# Power.net
KiCad netlist of a schematic drawn in Altium Designer
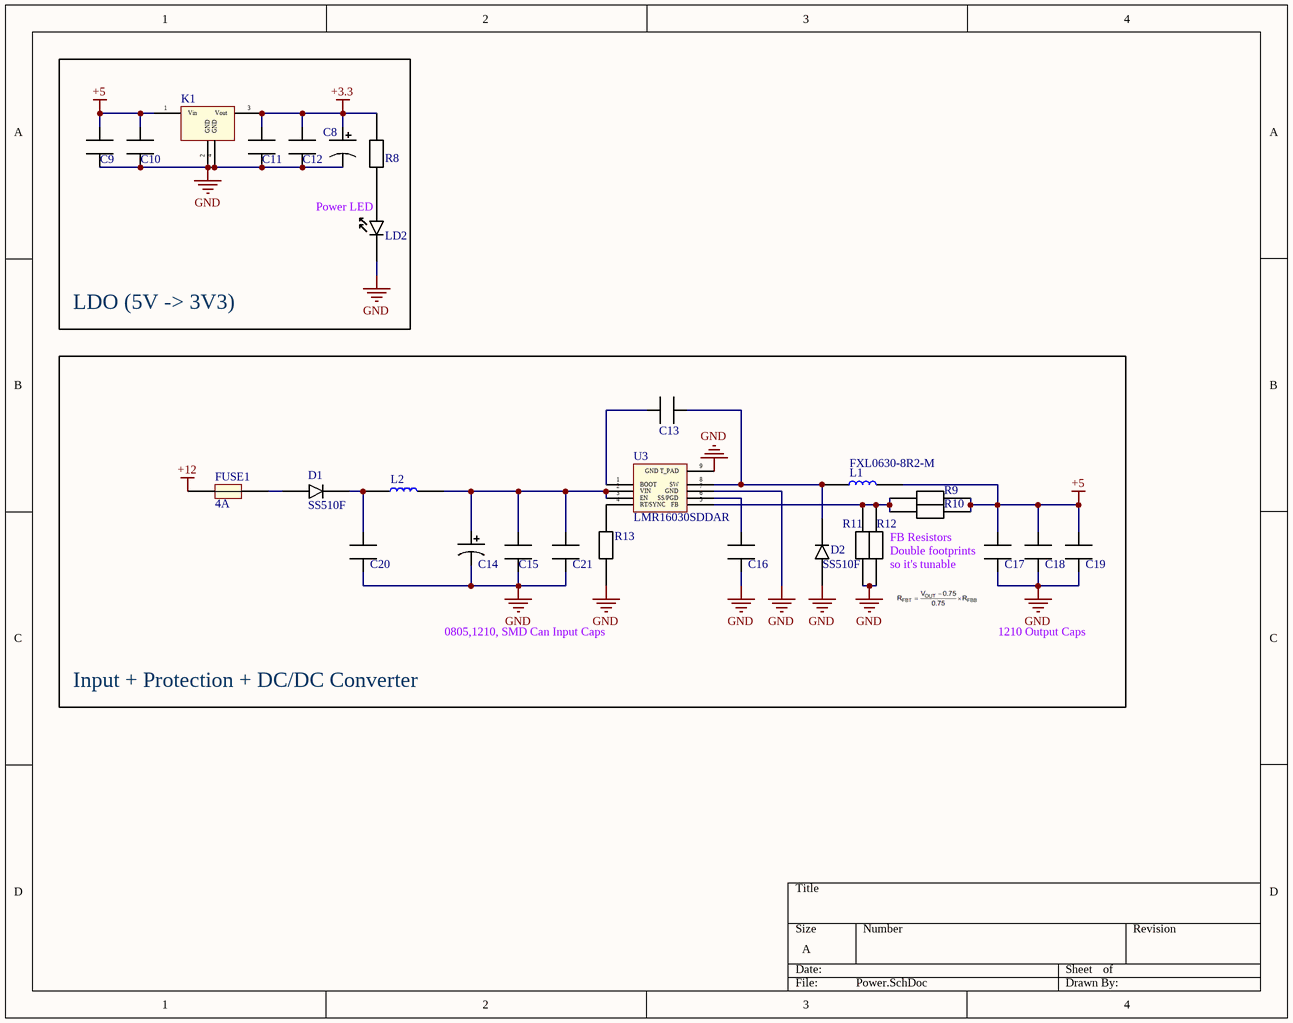
[diagram p0: Power.SchDoc]

(export (version "E")
  (design (tool "Eeschema 10.0.6"))
  (components
    (comp (ref "C8")
      (value "10uf")
      (footprint "CAP_CAN_D5MM")
      (description "SMD Can Capacitor; 5mm Diameter")
      (libsource (lib "Passives") (part "CAP_CAN_D5mm"))
    )
    (comp (ref "C9")
      (value "1uF")
      (footprint "CAP_1206")
      (description "CAP_1206")
      (libsource (lib "Passives") (part "CAP_1206"))
    )
    (comp (ref "C10")
      (value "100nF")
      (footprint "CAP_0805")
      (description "CAP_0805")
      (libsource (lib "Passives") (part "CAP_0805"))
    )
    (comp (ref "C11")
      (value "100nF")
      (footprint "CAP_0805")
      (description "CAP_0805")
      (libsource (lib "Passives") (part "CAP_0805"))
    )
    (comp (ref "C12")
      (value "1uF")
      (footprint "CAP_1206")
      (description "CAP_1206")
      (libsource (lib "Passives") (part "CAP_1206"))
    )
    (comp (ref "C13")
      (value "100nF 50V")
      (footprint "CAP_0805")
      (description "CAP_0805")
      (libsource (lib "Passives") (part "CAP_0805"))
    )
    (comp (ref "C14")
      (value "47uf 100v")
      (footprint "CAP_CAN_D10mm")
      (description "SMD Can Capacitor; 10mm Diameter")
      (libsource (lib "Passives") (part "CAP_CAN_D10mm"))
    )
    (comp (ref "C15")
      (value "10uF 100V")
      (footprint "CAP_1210")
      (description "CAP_1210")
      (libsource (lib "Passives") (part "CAP_1210"))
    )
    (comp (ref "C16")
      (value "100nF 50V")
      (footprint "CAP_0805")
      (description "CAP_0805")
      (libsource (lib "Passives") (part "CAP_0805"))
    )
    (comp (ref "C17")
      (value "CS3225X7R476K160NRL")
      (footprint "CAP_1210")
      (description "CAP_1210")
      (libsource (lib "Passives") (part "CAP_1210"))
    )
    (comp (ref "C18")
      (value "CS3225X7R476K160NRL")
      (footprint "CAP_1210")
      (description "CAP_1210")
      (libsource (lib "Passives") (part "CAP_1210"))
    )
    (comp (ref "C19")
      (value "CS3225X7R476K160NRL")
      (footprint "CAP_1210")
      (description "CAP_1210")
      (libsource (lib "Passives") (part "CAP_1210"))
    )
    (comp (ref "C20")
      (value "100nF 100V")
      (footprint "CAP_0805")
      (description "CAP_0805")
      (libsource (lib "Passives") (part "CAP_0805"))
    )
    (comp (ref "C21")
      (value "100nF 100V")
      (footprint "CAP_0805")
      (description "CAP_0805")
      (libsource (lib "Passives") (part "CAP_0805"))
    )
    (comp (ref "D1")
      (value "SS510F")
      (footprint "SMAF")
      (description "100V 850mV@5A 5A SMAF Schottky Diodes ROHS")
      (libsource (lib "Diodes") (part "SS510F"))
    )
    (comp (ref "D2")
      (value "SS510F")
      (footprint "SMAF")
      (description "100V 850mV@5A 5A SMAF Schottky Diodes ROHS")
      (libsource (lib "Diodes") (part "SS510F"))
    )
    (comp (ref "FUSE1")
      (value "4A")
      (footprint "FUSE_1206")
      (description "Fuse_1206")
      (libsource (lib "Passives") (part "Fuse_1206"))
    )
    (comp (ref "K1")
      (value "MIC39100-3.3WS")
      (footprint "SOT223-4")
      (description "LDO; \r\n2.25V -> 16V;\r\n1A Max; \r\nFixed Output - 1.8V, 2.5V, 3.3V, 5V")
      (libsource (lib "IC_Power") (part "MIC39100_SOT223"))
    )
    (comp (ref "L1")
      (value "FXL0630-8R2-M")
      (footprint "IND_FXL06")
      (description "Precision Wire Wound Inductor, 2-Leads, Body 4,50x4,00mm, IPC Medium Density")
      (libsource (lib "Passives") (part "IND_FXL06"))
    )
    (comp (ref "L2")
      (value "10uH 1.2A")
      (footprint "IND_1210")
      (description "Precision Wire Wound Inductor, 2-Leads, Body 4,50x4,00mm, IPC Medium Density")
      (libsource (lib "Passives") (part "IND_1210_Choke"))
    )
    (comp (ref "LD2")
      (value "LED_0805")
      (footprint "LED_0805")
      (libsource (lib "Passives") (part "LED_0805"))
    )
    (comp (ref "R8")
      (value "10k")
      (footprint "RES_0805")
      (description "RES_0805")
      (libsource (lib "Passives") (part "RES_0805"))
    )
    (comp (ref "R9")
      (value "10k")
      (footprint "RES_0805")
      (description "RES_0805")
      (libsource (lib "Passives") (part "RES_0805"))
    )
    (comp (ref "R10")
      (value "NC")
      (footprint "RES_0805")
      (description "RES_0805")
      (libsource (lib "Passives") (part "RES_0805"))
    )
    (comp (ref "R11")
      (value "2k")
      (footprint "RES_0805")
      (description "RES_0805")
      (libsource (lib "Passives") (part "RES_0805"))
    )
    (comp (ref "R12")
      (value "15k")
      (footprint "RES_0805")
      (description "RES_0805")
      (libsource (lib "Passives") (part "RES_0805"))
    )
    (comp (ref "R13")
      (value "10k")
      (footprint "RES_0805")
      (description "RES_0805")
      (libsource (lib "Passives") (part "RES_0805"))
    )
    (comp (ref "U3")
      (value "LMR16030SDDAR")
      (footprint "SOIC8_T")
      (libsource (lib "IC_Power") (part "TI LMR16030SDDAR"))
    )
  )
  (nets
    (net (code "1") (name "+3.3") (class "Default")
      (node (ref "C11") (pin "2") (pinfunction "2_2") (pintype "passive"))
      (node (ref "C12") (pin "2") (pinfunction "2_2") (pintype "passive"))
      (node (ref "C8") (pin "1") (pinfunction "1_1") (pintype "passive"))
      (node (ref "K1") (pin "3") (pinfunction "Vout_3") (pintype "passive"))
      (node (ref "R8") (pin "2") (pinfunction "2_2") (pintype "passive"))
    )
    (net (code "2") (name "+5") (class "Default")
      (node (ref "C10") (pin "2") (pinfunction "2_2") (pintype "passive"))
      (node (ref "C17") (pin "2") (pinfunction "2_2") (pintype "passive"))
      (node (ref "C18") (pin "2") (pinfunction "2_2") (pintype "passive"))
      (node (ref "C19") (pin "2") (pinfunction "2_2") (pintype "passive"))
      (node (ref "C9") (pin "2") (pinfunction "2_2") (pintype "passive"))
      (node (ref "K1") (pin "1") (pinfunction "Vin_1") (pintype "passive"))
      (node (ref "L1") (pin "2") (pinfunction "2_2") (pintype "passive"))
      (node (ref "R10") (pin "2") (pinfunction "2_2") (pintype "passive"))
      (node (ref "R9") (pin "2") (pinfunction "2_2") (pintype "passive"))
    )
    (net (code "3") (name "+12") (class "Default")
      (node (ref "FUSE1") (pin "1") (pinfunction "1_1") (pintype "passive"))
    )
    (net (code "4") (name "GND") (class "Default")
      (node (ref "C10") (pin "1") (pinfunction "1_1") (pintype "passive"))
      (node (ref "C11") (pin "1") (pinfunction "1_1") (pintype "passive"))
      (node (ref "C12") (pin "1") (pinfunction "1_1") (pintype "passive"))
      (node (ref "C14") (pin "2") (pinfunction "2_2") (pintype "passive"))
      (node (ref "C15") (pin "1") (pinfunction "1_1") (pintype "passive"))
      (node (ref "C16") (pin "1") (pinfunction "1_1") (pintype "passive"))
      (node (ref "C17") (pin "1") (pinfunction "1_1") (pintype "passive"))
      (node (ref "C18") (pin "1") (pinfunction "1_1") (pintype "passive"))
      (node (ref "C19") (pin "1") (pinfunction "1_1") (pintype "passive"))
      (node (ref "C20") (pin "1") (pinfunction "1_1") (pintype "passive"))
      (node (ref "C21") (pin "1") (pinfunction "1_1") (pintype "passive"))
      (node (ref "C8") (pin "2") (pinfunction "2_2") (pintype "passive"))
      (node (ref "C9") (pin "1") (pinfunction "1_1") (pintype "passive"))
      (node (ref "D2") (pin "2") (pinfunction "2_2") (pintype "passive"))
      (node (ref "K1") (pin "2") (pinfunction "GND_2") (pintype "passive"))
      (node (ref "K1") (pin "4") (pinfunction "GND_4") (pintype "passive"))
      (node (ref "LD2") (pin "1") (pinfunction "1_1") (pintype "passive"))
      (node (ref "R11") (pin "2") (pinfunction "2_2") (pintype "passive"))
      (node (ref "R12") (pin "2") (pinfunction "2_2") (pintype "passive"))
      (node (ref "R13") (pin "1") (pinfunction "1_1") (pintype "passive"))
      (node (ref "U3") (pin "7") (pinfunction "GND_7") (pintype "passive"))
      (node (ref "U3") (pin "9") (pinfunction "GND_T_PAD_9") (pintype "passive"))
    )
    (net (code "5") (name "Net-(C20-Pad2)") (class "Default")
      (node (ref "C20") (pin "2") (pinfunction "2_2") (pintype "passive"))
      (node (ref "D1") (pin "1") (pinfunction "1_1") (pintype "passive"))
      (node (ref "L2") (pin "1") (pinfunction "1_1") (pintype "passive"))
    )
    (net (code "6") (name "Net-(D1-Pad2)") (class "Default")
      (node (ref "D1") (pin "2") (pinfunction "2_2") (pintype "passive"))
      (node (ref "FUSE1") (pin "2") (pinfunction "2_2") (pintype "passive"))
    )
    (net (code "7") (name "Net-(LD2-Pad2)") (class "Default")
      (node (ref "LD2") (pin "2") (pinfunction "2_2") (pintype "passive"))
      (node (ref "R8") (pin "1") (pinfunction "1_1") (pintype "passive"))
    )
    (net (code "8") (name "Net-(U3-BOOT)") (class "Default")
      (node (ref "C13") (pin "1") (pinfunction "1_1") (pintype "passive"))
      (node (ref "U3") (pin "1") (pinfunction "BOOT_1") (pintype "passive"))
    )
    (net (code "9") (name "Net-(U3-EN)") (class "Default")
      (node (ref "C14") (pin "1") (pinfunction "1_1") (pintype "passive"))
      (node (ref "C15") (pin "2") (pinfunction "2_2") (pintype "passive"))
      (node (ref "C21") (pin "2") (pinfunction "2_2") (pintype "passive"))
      (node (ref "L2") (pin "2") (pinfunction "2_2") (pintype "passive"))
      (node (ref "U3") (pin "2") (pinfunction "VIN_2") (pintype "passive"))
      (node (ref "U3") (pin "3") (pinfunction "EN_3") (pintype "passive"))
    )
    (net (code "10") (name "Net-(U3-FB)") (class "Default")
      (node (ref "R10") (pin "1") (pinfunction "1_1") (pintype "passive"))
      (node (ref "R11") (pin "1") (pinfunction "1_1") (pintype "passive"))
      (node (ref "R12") (pin "1") (pinfunction "1_1") (pintype "passive"))
      (node (ref "R9") (pin "1") (pinfunction "1_1") (pintype "passive"))
      (node (ref "U3") (pin "5") (pinfunction "FB_5") (pintype "passive"))
    )
    (net (code "11") (name "Net-(U3-RT{slash}SYNC)") (class "Default")
      (node (ref "R13") (pin "2") (pinfunction "2_2") (pintype "passive"))
      (node (ref "U3") (pin "4") (pinfunction "RT/SYNC_4") (pintype "passive"))
    )
    (net (code "12") (name "Net-(U3-SS{slash}PGD)") (class "Default")
      (node (ref "C16") (pin "2") (pinfunction "2_2") (pintype "passive"))
      (node (ref "U3") (pin "6") (pinfunction "SS/PGD_6") (pintype "passive"))
    )
    (net (code "13") (name "Net-(U3-SW)") (class "Default")
      (node (ref "C13") (pin "2") (pinfunction "2_2") (pintype "passive"))
      (node (ref "D2") (pin "1") (pinfunction "1_1") (pintype "passive"))
      (node (ref "L1") (pin "1") (pinfunction "1_1") (pintype "passive"))
      (node (ref "U3") (pin "8") (pinfunction "SW_8") (pintype "passive"))
    )
  )
)
